# rapidshark-half-assed-half-h-bridge-mk-2.net
KiCad netlist of a schematic drawn in EAGLE
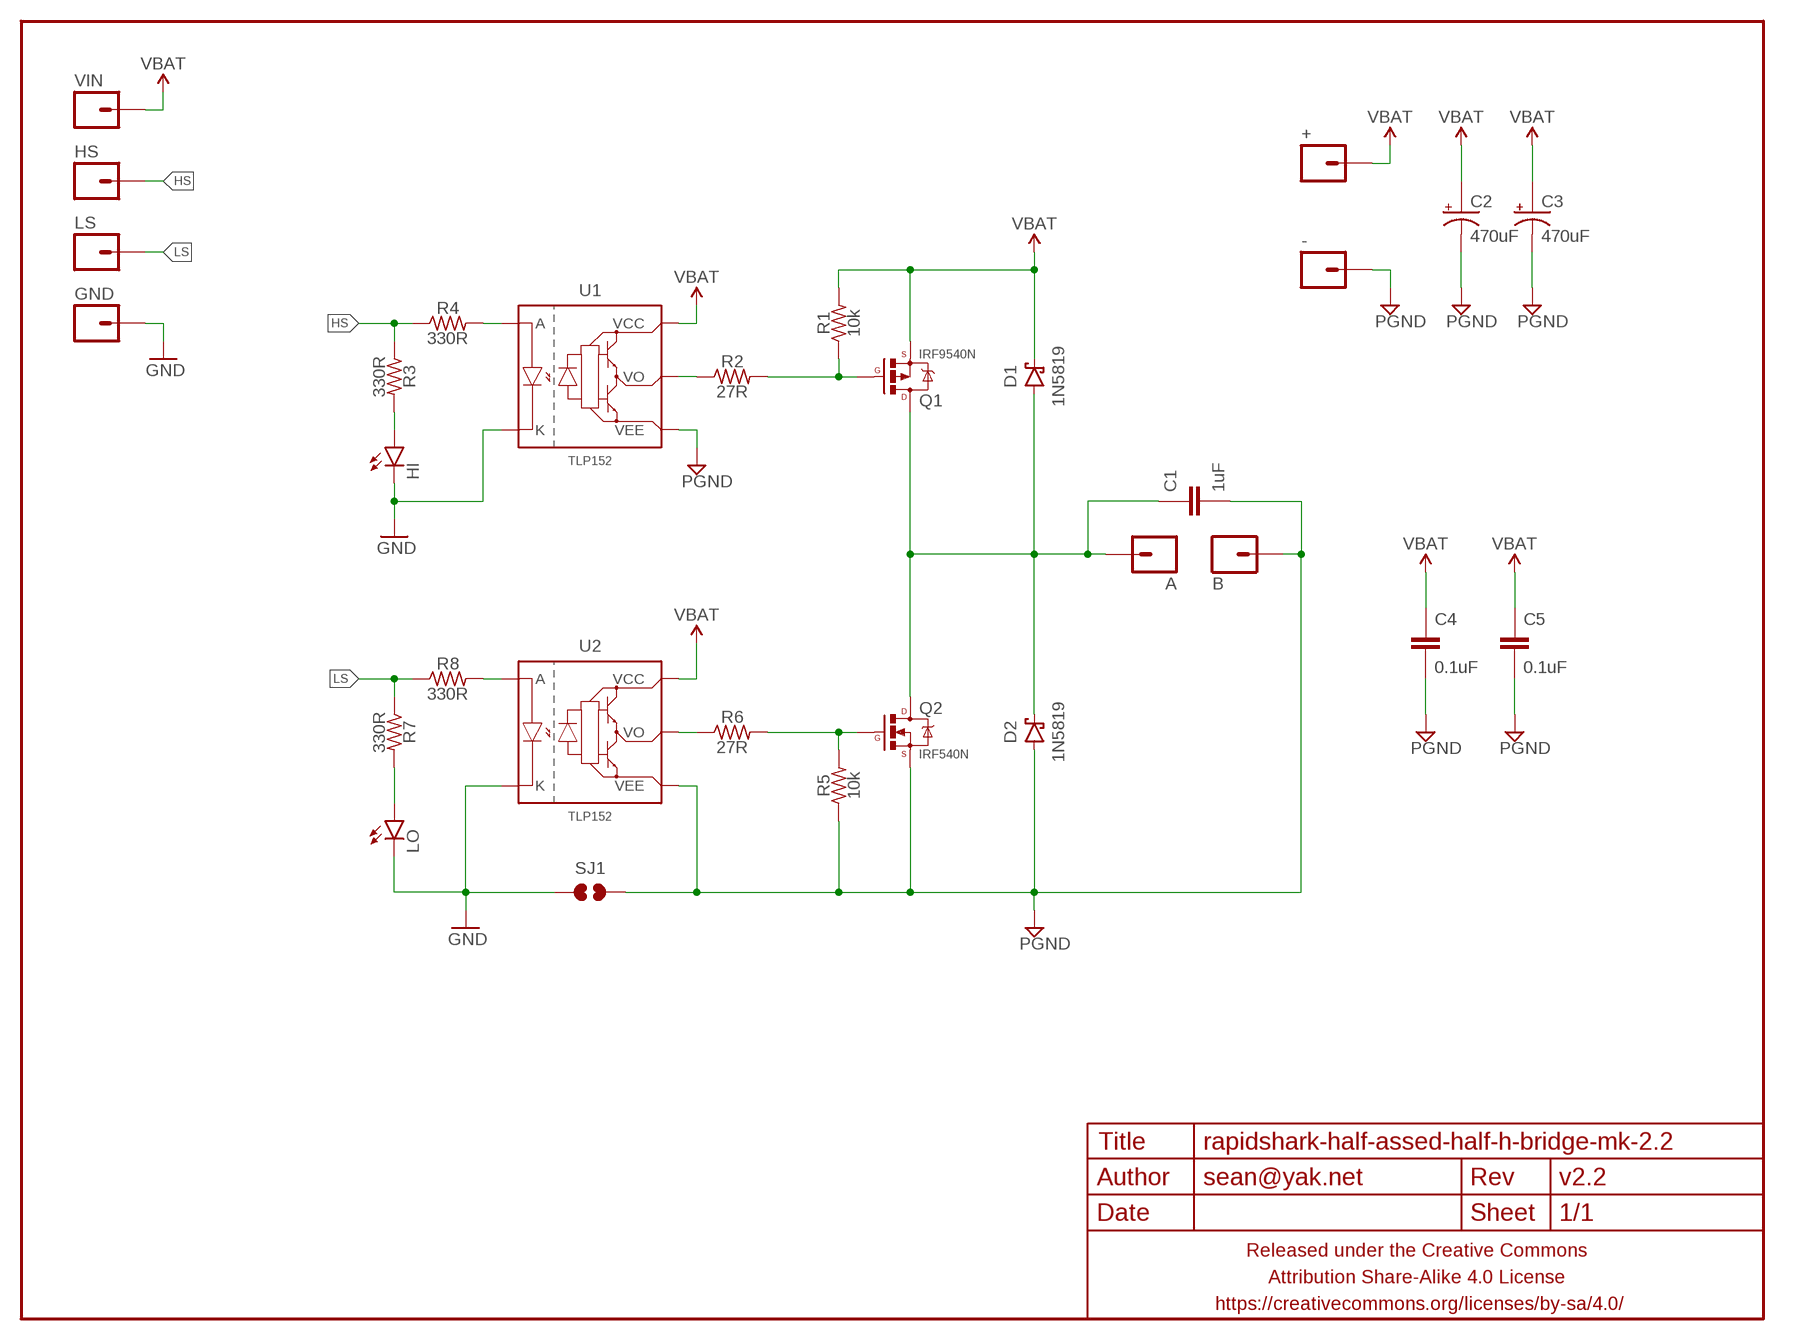
[diagram p0: schematic, sheet 1]

(export (version "E")
  (design (tool "Eeschema 10.0.6"))
  (components
    (comp (ref "+")
      (value "M01PTH-1.9MM")
      (footprint "eagle-import:1X01-1.9MM-CIR")
      (libsource (lib "eagle-import") (part "M01PTH-1.9MM"))
    )
    (comp (ref "-")
      (value "M01PTH-1.9MM")
      (footprint "eagle-import:1X01-1.9MM-CIR")
      (libsource (lib "eagle-import") (part "M01PTH-1.9MM"))
    )
    (comp (ref "A")
      (value "M01PTH-1.9MM")
      (footprint "eagle-import:1X01-1.9MM-CIR")
      (libsource (lib "eagle-import") (part "M01PTH-1.9MM"))
    )
    (comp (ref "B")
      (value "M01PTH-1.9MM")
      (footprint "eagle-import:1X01-1.9MM-CIR")
      (libsource (lib "eagle-import") (part "M01PTH-1.9MM"))
    )
    (comp (ref "C1")
      (value "1uF")
      (footprint "eagle-import:C0603-TIGHTER")
      (libsource (lib "eagle-import") (part "CAPACITOR-CERAMICC0603-TIGHTER"))
    )
    (comp (ref "C2")
      (value "470uF")
      (footprint "eagle-import:E5-10,5")
      (libsource (lib "eagle-import") (part "CAPACITOR-POLARIZEDE5-10.5"))
    )
    (comp (ref "C3")
      (value "470uF")
      (footprint "eagle-import:E5-10,5")
      (libsource (lib "eagle-import") (part "CAPACITOR-POLARIZEDE5-10.5"))
    )
    (comp (ref "C4")
      (value "0.1uF")
      (footprint "eagle-import:C0603-TIGHTER")
      (libsource (lib "eagle-import") (part "CAPACITOR-CERAMICC0603-TIGHTER"))
    )
    (comp (ref "C5")
      (value "0.1uF")
      (footprint "eagle-import:C0603-TIGHTER")
      (libsource (lib "eagle-import") (part "CAPACITOR-CERAMICC0603-TIGHTER"))
    )
    (comp (ref "D1")
      (value "1N5819")
      (footprint "eagle-import:SMA-DIODE-SCHOTTKY")
      (libsource (lib "eagle-import") (part "DIODE-SCHOTTKYSMA"))
    )
    (comp (ref "D2")
      (value "1N5819")
      (footprint "eagle-import:SMA-DIODE-SCHOTTKY")
      (libsource (lib "eagle-import") (part "DIODE-SCHOTTKYSMA"))
    )
    (comp (ref "FRAME1")
      (value "FRAME-LETTERNO_PACKAGE")
      (footprint "eagle-import:DUMMY")
      (fields (field (name "DESIGNER") "sean@yak.net") (field (name "VERSION") "v2.2"))
      (libsource (lib "eagle-import") (part "FRAME-LETTERNO_PACKAGE"))
    )
    (comp (ref "GND")
      (value "M01PTH")
      (footprint "eagle-import:1X01")
      (libsource (lib "eagle-import") (part "M01PTH"))
    )
    (comp (ref "HI")
      (value "LED0603-TIGHT")
      (footprint "eagle-import:LED-0603-TIGHT")
      (libsource (lib "eagle-import") (part "LED0603-TIGHT"))
    )
    (comp (ref "HS")
      (value "M01PTH")
      (footprint "eagle-import:1X01")
      (libsource (lib "eagle-import") (part "M01PTH"))
    )
    (comp (ref "LO")
      (value "LED0603-TIGHT")
      (footprint "eagle-import:LED-0603-TIGHT")
      (libsource (lib "eagle-import") (part "LED0603-TIGHT"))
    )
    (comp (ref "LS")
      (value "M01PTH")
      (footprint "eagle-import:1X01")
      (libsource (lib "eagle-import") (part "M01PTH"))
    )
    (comp (ref "Q1")
      (value "IRF9540N")
      (footprint "eagle-import:D2PAK")
      (libsource (lib "eagle-import") (part "MOSFET-PCHANNELD2PAK"))
    )
    (comp (ref "Q2")
      (value "IRF540N")
      (footprint "eagle-import:D2PAK")
      (libsource (lib "eagle-import") (part "MOSFET-NCHANNELD2PAK"))
    )
    (comp (ref "R1")
      (value "10k")
      (footprint "eagle-import:R0603-TIGHTER")
      (libsource (lib "eagle-import") (part "RESISTORR0603-TIGHTER"))
    )
    (comp (ref "R2")
      (value "27R")
      (footprint "eagle-import:R0603-TIGHTER")
      (libsource (lib "eagle-import") (part "RESISTORR0603-TIGHTER"))
    )
    (comp (ref "R3")
      (value "330R")
      (footprint "eagle-import:R0603-TIGHTER")
      (libsource (lib "eagle-import") (part "RESISTORR0603-TIGHTER"))
    )
    (comp (ref "R4")
      (value "330R")
      (footprint "eagle-import:R0603-TIGHTER")
      (libsource (lib "eagle-import") (part "RESISTORR0603-TIGHTER"))
    )
    (comp (ref "R5")
      (value "10k")
      (footprint "eagle-import:R0603-TIGHTER")
      (libsource (lib "eagle-import") (part "RESISTORR0603-TIGHTER"))
    )
    (comp (ref "R6")
      (value "27R")
      (footprint "eagle-import:R0603-TIGHTER")
      (libsource (lib "eagle-import") (part "RESISTORR0603-TIGHTER"))
    )
    (comp (ref "R7")
      (value "330R")
      (footprint "eagle-import:R0603-TIGHTER")
      (libsource (lib "eagle-import") (part "RESISTORR0603-TIGHTER"))
    )
    (comp (ref "R8")
      (value "330R")
      (footprint "eagle-import:R0603-TIGHTER")
      (libsource (lib "eagle-import") (part "RESISTORR0603-TIGHTER"))
    )
    (comp (ref "SJ1")
      (value "JUMPER-PAD-2-NO")
      (footprint "eagle-import:PAD-JUMPER-2-NO_NO_SILK")
      (libsource (lib "eagle-import") (part "JUMPER-PAD-2-NO"))
    )
    (comp (ref "U1")
      (value "TLP152")
      (footprint "eagle-import:SO05")
      (libsource (lib "eagle-import") (part "OPTOISOLATOR-GATEDRIVERSOIC05"))
    )
    (comp (ref "U2")
      (value "TLP152")
      (footprint "eagle-import:SO05")
      (libsource (lib "eagle-import") (part "OPTOISOLATOR-GATEDRIVERSOIC05"))
    )
    (comp (ref "VIN")
      (value "M01PTH")
      (footprint "eagle-import:1X01")
      (libsource (lib "eagle-import") (part "M01PTH"))
    )
  )
  (nets
    (net (code "1") (name "GND") (class "Default")
      (node (ref "GND") (pin "1") (pinfunction "1_1") (pintype "passive"))
      (node (ref "HI") (pin "C") (pinfunction "C_C") (pintype "passive"))
      (node (ref "LO") (pin "C") (pinfunction "C_C") (pintype "passive"))
      (node (ref "SJ1") (pin "1") (pinfunction "1_1") (pintype "passive"))
      (node (ref "U1") (pin "3") (pinfunction "K_3") (pintype "bidirectional"))
      (node (ref "U2") (pin "3") (pinfunction "K_3") (pintype "bidirectional"))
    )
    (net (code "2") (name "HS") (class "Default")
      (node (ref "HS") (pin "1") (pinfunction "1_1") (pintype "passive"))
      (node (ref "R3") (pin "1") (pinfunction "1_1") (pintype "passive"))
      (node (ref "R4") (pin "1") (pinfunction "1_1") (pintype "passive"))
    )
    (net (code "3") (name "LS") (class "Default")
      (node (ref "LS") (pin "1") (pinfunction "1_1") (pintype "passive"))
      (node (ref "R7") (pin "1") (pinfunction "1_1") (pintype "passive"))
      (node (ref "R8") (pin "1") (pinfunction "1_1") (pintype "passive"))
    )
    (net (code "4") (name "Net-(A-1)") (class "Default")
      (node (ref "A") (pin "P$1") (pinfunction "1_P$1") (pintype "passive"))
      (node (ref "C1") (pin "1") (pinfunction "1_1") (pintype "passive"))
      (node (ref "D1") (pin "A") (pinfunction "A_A") (pintype "passive"))
      (node (ref "D2") (pin "C") (pinfunction "C_C") (pintype "passive"))
      (node (ref "Q1") (pin "D") (pinfunction "D_D") (pintype "passive"))
      (node (ref "Q2") (pin "D") (pinfunction "D_D") (pintype "passive"))
    )
    (net (code "5") (name "Net-(HI-PadA)") (class "Default")
      (node (ref "HI") (pin "A") (pinfunction "A_A") (pintype "passive"))
      (node (ref "R3") (pin "2") (pinfunction "2_2") (pintype "passive"))
    )
    (net (code "6") (name "Net-(LO-PadA)") (class "Default")
      (node (ref "LO") (pin "A") (pinfunction "A_A") (pintype "passive"))
      (node (ref "R7") (pin "2") (pinfunction "2_2") (pintype "passive"))
    )
    (net (code "7") (name "Net-(Q1-PadG)") (class "Default")
      (node (ref "Q1") (pin "G") (pinfunction "G_G") (pintype "passive"))
      (node (ref "R1") (pin "1") (pinfunction "1_1") (pintype "passive"))
      (node (ref "R2") (pin "2") (pinfunction "2_2") (pintype "passive"))
    )
    (net (code "8") (name "Net-(Q2-PadG)") (class "Default")
      (node (ref "Q2") (pin "G") (pinfunction "G_G") (pintype "passive"))
      (node (ref "R5") (pin "2") (pinfunction "2_2") (pintype "passive"))
      (node (ref "R6") (pin "2") (pinfunction "2_2") (pintype "passive"))
    )
    (net (code "9") (name "Net-(U1-A)") (class "Default")
      (node (ref "R4") (pin "2") (pinfunction "2_2") (pintype "passive"))
      (node (ref "U1") (pin "1") (pinfunction "A_1") (pintype "bidirectional"))
    )
    (net (code "10") (name "Net-(U1-VO)") (class "Default")
      (node (ref "R2") (pin "1") (pinfunction "1_1") (pintype "passive"))
      (node (ref "U1") (pin "5") (pinfunction "VO_5") (pintype "bidirectional"))
    )
    (net (code "11") (name "Net-(U2-A)") (class "Default")
      (node (ref "R8") (pin "2") (pinfunction "2_2") (pintype "passive"))
      (node (ref "U2") (pin "1") (pinfunction "A_1") (pintype "bidirectional"))
    )
    (net (code "12") (name "Net-(U2-VO)") (class "Default")
      (node (ref "R6") (pin "1") (pinfunction "1_1") (pintype "passive"))
      (node (ref "U2") (pin "5") (pinfunction "VO_5") (pintype "bidirectional"))
    )
    (net (code "13") (name "PGND") (class "Default")
      (node (ref "-") (pin "P$1") (pinfunction "1_P$1") (pintype "passive"))
      (node (ref "B") (pin "P$1") (pinfunction "1_P$1") (pintype "passive"))
      (node (ref "C1") (pin "2") (pinfunction "2_2") (pintype "passive"))
      (node (ref "C2") (pin "-") (pinfunction "-_-") (pintype "passive"))
      (node (ref "C3") (pin "-") (pinfunction "-_-") (pintype "passive"))
      (node (ref "C4") (pin "2") (pinfunction "2_2") (pintype "passive"))
      (node (ref "C5") (pin "2") (pinfunction "2_2") (pintype "passive"))
      (node (ref "D2") (pin "A") (pinfunction "A_A") (pintype "passive"))
      (node (ref "Q2") (pin "S") (pinfunction "S_S") (pintype "passive"))
      (node (ref "R5") (pin "1") (pinfunction "1_1") (pintype "passive"))
      (node (ref "SJ1") (pin "2") (pinfunction "2_2") (pintype "passive"))
      (node (ref "U1") (pin "4") (pinfunction "VEE_4") (pintype "bidirectional"))
      (node (ref "U2") (pin "4") (pinfunction "VEE_4") (pintype "bidirectional"))
    )
    (net (code "14") (name "VBAT") (class "Default")
      (node (ref "+") (pin "P$1") (pinfunction "1_P$1") (pintype "passive"))
      (node (ref "C2") (pin "+") (pinfunction "+_+") (pintype "passive"))
      (node (ref "C3") (pin "+") (pinfunction "+_+") (pintype "passive"))
      (node (ref "C4") (pin "1") (pinfunction "1_1") (pintype "passive"))
      (node (ref "C5") (pin "1") (pinfunction "1_1") (pintype "passive"))
      (node (ref "D1") (pin "C") (pinfunction "C_C") (pintype "passive"))
      (node (ref "Q1") (pin "S") (pinfunction "S_S") (pintype "passive"))
      (node (ref "R1") (pin "2") (pinfunction "2_2") (pintype "passive"))
      (node (ref "U1") (pin "6") (pinfunction "VCC_6") (pintype "bidirectional"))
      (node (ref "U2") (pin "6") (pinfunction "VCC_6") (pintype "bidirectional"))
      (node (ref "VIN") (pin "1") (pinfunction "1_1") (pintype "passive"))
    )
  )
)
